# DualDriverStepperRight.net
KiCad netlist of a schematic drawn in Altium Designer
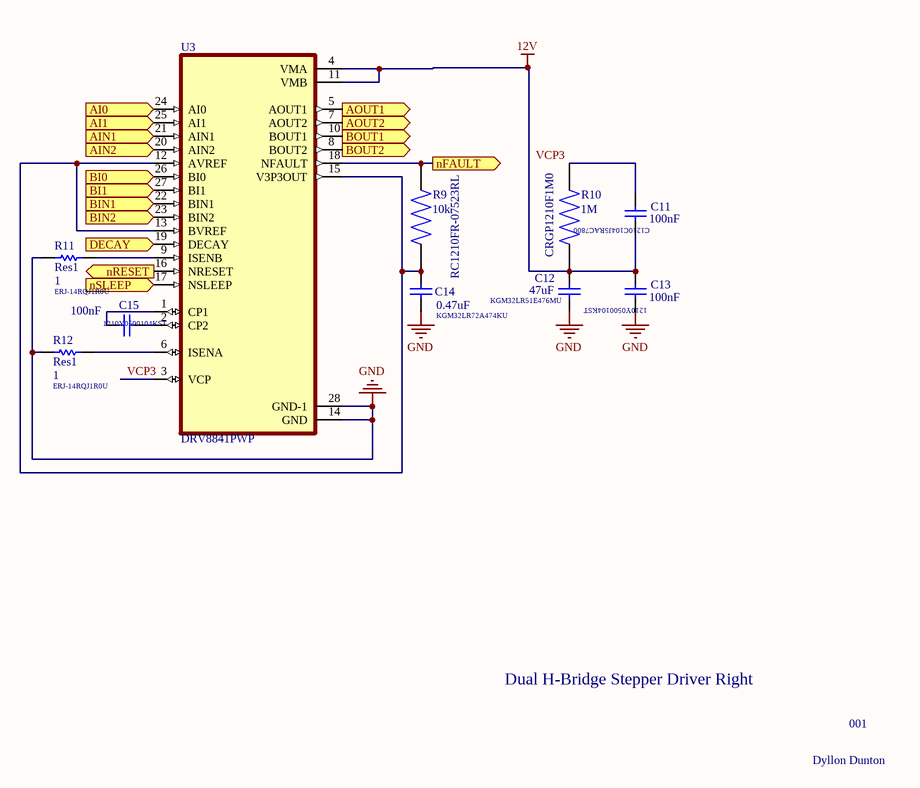
[diagram p0: DualDriverStepperRight.SchDoc]

(export (version "E")
  (design (tool "Eeschema 10.0.6"))
  (components
    (comp (ref "C11")
      (value "100nF")
      (footprint "C1210")
      (description "Capacitor")
      (fields (field (name "Comment") "Cap") (field (name "PUBLISHER") "Altium Limited"))
      (libsource (lib "Miscellaneous Devices") (part "Cap"))
    )
    (comp (ref "C12")
      (value "47uF")
      (footprint "C1210")
      (description "Capacitor")
      (fields (field (name "Comment") "Cap") (field (name "PUBLISHER") "Altium Limited"))
      (libsource (lib "Miscellaneous Devices") (part "Cap"))
    )
    (comp (ref "C13")
      (value "100nF")
      (footprint "C1210")
      (description "Capacitor")
      (fields (field (name "Comment") "Cap") (field (name "PUBLISHER") "Altium Limited"))
      (libsource (lib "Miscellaneous Devices") (part "Cap"))
    )
    (comp (ref "C14")
      (value "0.47uF")
      (footprint "C1210")
      (description "Capacitor")
      (fields (field (name "Comment") "Cap") (field (name "PUBLISHER") "Altium Limited"))
      (libsource (lib "Miscellaneous Devices") (part "Cap"))
    )
    (comp (ref "C15")
      (value "100nF")
      (footprint "C1210")
      (description "Capacitor")
      (fields (field (name "Comment") "Cap") (field (name "PUBLISHER") "Altium Limited"))
      (libsource (lib "Miscellaneous Devices") (part "Cap"))
    )
    (comp (ref "R9")
      (value "RC1210FR-07523RL")
      (footprint "RESC3126X65N")
      (description "523 Ohms Â±1% 0.5W, 1/2W Chip Resistor 1210 _3225 Metric_ Moisture Resistant Thick Film")
      (fields (field (name "MF") "Yageo") (field (name "ALTIUM_VALUE") "10k"))
      (libsource (lib "RC1210FR-07523RL") (part "RC1210FR-07523RL"))
    )
    (comp (ref "R10")
      (value "CRGP1210F1M0")
      (footprint "RESC3126X65N")
      (description "523 Ohms Â±1% 0.5W, 1/2W Chip Resistor 1210 _3225 Metric_ Moisture Resistant Thick Film")
      (fields
        (field (name "MF") "Yageo")
        (field (name "ALTIUM_VALUE") "1M")
        (field (name "MP") "RC1210FR-07523RL")
      )
      (libsource (lib "RC1210FR-07523RL") (part "RC1210FR-07523RL"))
    )
    (comp (ref "R11")
      (value "Res1")
      (footprint "RES_ERJ14RQJ1R0U")
      (description "Resistor")
      (fields (field (name "ALTIUM_VALUE") "1") (field (name "PUBLISHER") "Altium Limited"))
      (libsource (lib "Miscellaneous Devices") (part "Res1"))
    )
    (comp (ref "R12")
      (value "Res1")
      (footprint "RES_ERJ14RQJ1R0U")
      (description "Resistor")
      (fields (field (name "ALTIUM_VALUE") "1") (field (name "PUBLISHER") "Altium Limited"))
      (libsource (lib "Miscellaneous Devices") (part "Res1"))
    )
    (comp (ref "U3")
      (value "DRV8841PWP")
      (footprint "IC_TPS61196PWPRQ1")
      (fields (field (name "MF") "Texas Instruments"))
      (libsource (lib "DRV8841PWP") (part "DRV8841PWP"))
    )
  )
  (nets
    (net (code "1") (name "/AI0") (class "Default")
      (node (ref "U3") (pin "24") (pinfunction "AI0_24") (pintype "input"))
    )
    (net (code "2") (name "/AI1") (class "Default")
      (node (ref "U3") (pin "25") (pinfunction "AI1_25") (pintype "input"))
    )
    (net (code "3") (name "/AIN1") (class "Default")
      (node (ref "U3") (pin "21") (pinfunction "AIN1_21") (pintype "input"))
    )
    (net (code "4") (name "/AIN2") (class "Default")
      (node (ref "U3") (pin "20") (pinfunction "AIN2_20") (pintype "input"))
    )
    (net (code "5") (name "/AOUT1") (class "Default")
      (node (ref "U3") (pin "5") (pinfunction "AOUT1_5") (pintype "output"))
    )
    (net (code "6") (name "/AOUT2") (class "Default")
      (node (ref "U3") (pin "7") (pinfunction "AOUT2_7") (pintype "output"))
    )
    (net (code "7") (name "/BI0") (class "Default")
      (node (ref "U3") (pin "26") (pinfunction "BI0_26") (pintype "input"))
    )
    (net (code "8") (name "/BI1") (class "Default")
      (node (ref "U3") (pin "27") (pinfunction "BI1_27") (pintype "input"))
    )
    (net (code "9") (name "/BIN1") (class "Default")
      (node (ref "U3") (pin "22") (pinfunction "BIN1_22") (pintype "input"))
    )
    (net (code "10") (name "/BIN2") (class "Default")
      (node (ref "U3") (pin "23") (pinfunction "BIN2_23") (pintype "input"))
    )
    (net (code "11") (name "/BOUT1") (class "Default")
      (node (ref "U3") (pin "10") (pinfunction "BOUT1_10") (pintype "output"))
    )
    (net (code "12") (name "/BOUT2") (class "Default")
      (node (ref "U3") (pin "8") (pinfunction "BOUT2_8") (pintype "output"))
    )
    (net (code "13") (name "/DECAY") (class "Default")
      (node (ref "U3") (pin "19") (pinfunction "DECAY_19") (pintype "input"))
    )
    (net (code "14") (name "/VCP3") (class "Default")
      (node (ref "U3") (pin "3") (pinfunction "VCP_3") (pintype "bidirectional"))
    )
    (net (code "15") (name "/nFAULT") (class "Default")
      (node (ref "R9") (pin "2") (pinfunction "2_2") (pintype "passive"))
      (node (ref "U3") (pin "18") (pinfunction "NFAULT_18") (pintype "output"))
    )
    (net (code "16") (name "/nRESET") (class "Default")
      (node (ref "U3") (pin "16") (pinfunction "NRESET_16") (pintype "input"))
    )
    (net (code "17") (name "/nSLEEP") (class "Default")
      (node (ref "U3") (pin "17") (pinfunction "NSLEEP_17") (pintype "input"))
    )
    (net (code "18") (name "12V") (class "Default")
      (node (ref "C11") (pin "2") (pinfunction "2_2") (pintype "passive"))
      (node (ref "C12") (pin "2") (pinfunction "2_2") (pintype "passive"))
      (node (ref "C13") (pin "1") (pinfunction "1_1") (pintype "passive"))
      (node (ref "R10") (pin "1") (pinfunction "1_1") (pintype "passive"))
      (node (ref "U3") (pin "11") (pinfunction "VMB_11") (pintype "power_in"))
      (node (ref "U3") (pin "4") (pinfunction "VMA_4") (pintype "power_in"))
    )
    (net (code "19") (name "GND") (class "Default")
      (node (ref "C12") (pin "1") (pinfunction "1_1") (pintype "passive"))
      (node (ref "C13") (pin "2") (pinfunction "2_2") (pintype "passive"))
      (node (ref "C14") (pin "1") (pinfunction "1_1") (pintype "passive"))
      (node (ref "R11") (pin "1") (pinfunction "1_1") (pintype "passive"))
      (node (ref "R12") (pin "1") (pinfunction "1_1") (pintype "passive"))
      (node (ref "U3") (pin "14") (pinfunction "GND_14") (pintype "power_in"))
      (node (ref "U3") (pin "28") (pinfunction "GND-1_28") (pintype "power_in"))
    )
    (net (code "20") (name "Net-(C11-Pad1)") (class "Default")
      (node (ref "C11") (pin "1") (pinfunction "1_1") (pintype "passive"))
      (node (ref "R10") (pin "2") (pinfunction "2_2") (pintype "passive"))
    )
    (net (code "21") (name "Net-(U3-AVREF)") (class "Default")
      (node (ref "C14") (pin "2") (pinfunction "2_2") (pintype "passive"))
      (node (ref "R9") (pin "1") (pinfunction "1_1") (pintype "passive"))
      (node (ref "U3") (pin "12") (pinfunction "AVREF_12") (pintype "input"))
      (node (ref "U3") (pin "13") (pinfunction "BVREF_13") (pintype "input"))
      (node (ref "U3") (pin "15") (pinfunction "V3P3OUT_15") (pintype "output"))
    )
    (net (code "22") (name "Net-(U3-CP1)") (class "Default")
      (node (ref "C15") (pin "2") (pinfunction "2_2") (pintype "passive"))
      (node (ref "U3") (pin "1") (pinfunction "CP1_1") (pintype "bidirectional"))
    )
    (net (code "23") (name "Net-(U3-CP2)") (class "Default")
      (node (ref "C15") (pin "1") (pinfunction "1_1") (pintype "passive"))
      (node (ref "U3") (pin "2") (pinfunction "CP2_2") (pintype "bidirectional"))
    )
    (net (code "24") (name "Net-(U3-ISENA)") (class "Default")
      (node (ref "R12") (pin "2") (pinfunction "2_2") (pintype "passive"))
      (node (ref "U3") (pin "6") (pinfunction "ISENA_6") (pintype "bidirectional"))
    )
    (net (code "25") (name "Net-(U3-ISENB)") (class "Default")
      (node (ref "R11") (pin "2") (pinfunction "2_2") (pintype "passive"))
      (node (ref "U3") (pin "9") (pinfunction "ISENB_9") (pintype "input"))
    )
  )
)
